# Beam_ADC.net
KiCad netlist of a schematic drawn in Altium Designer
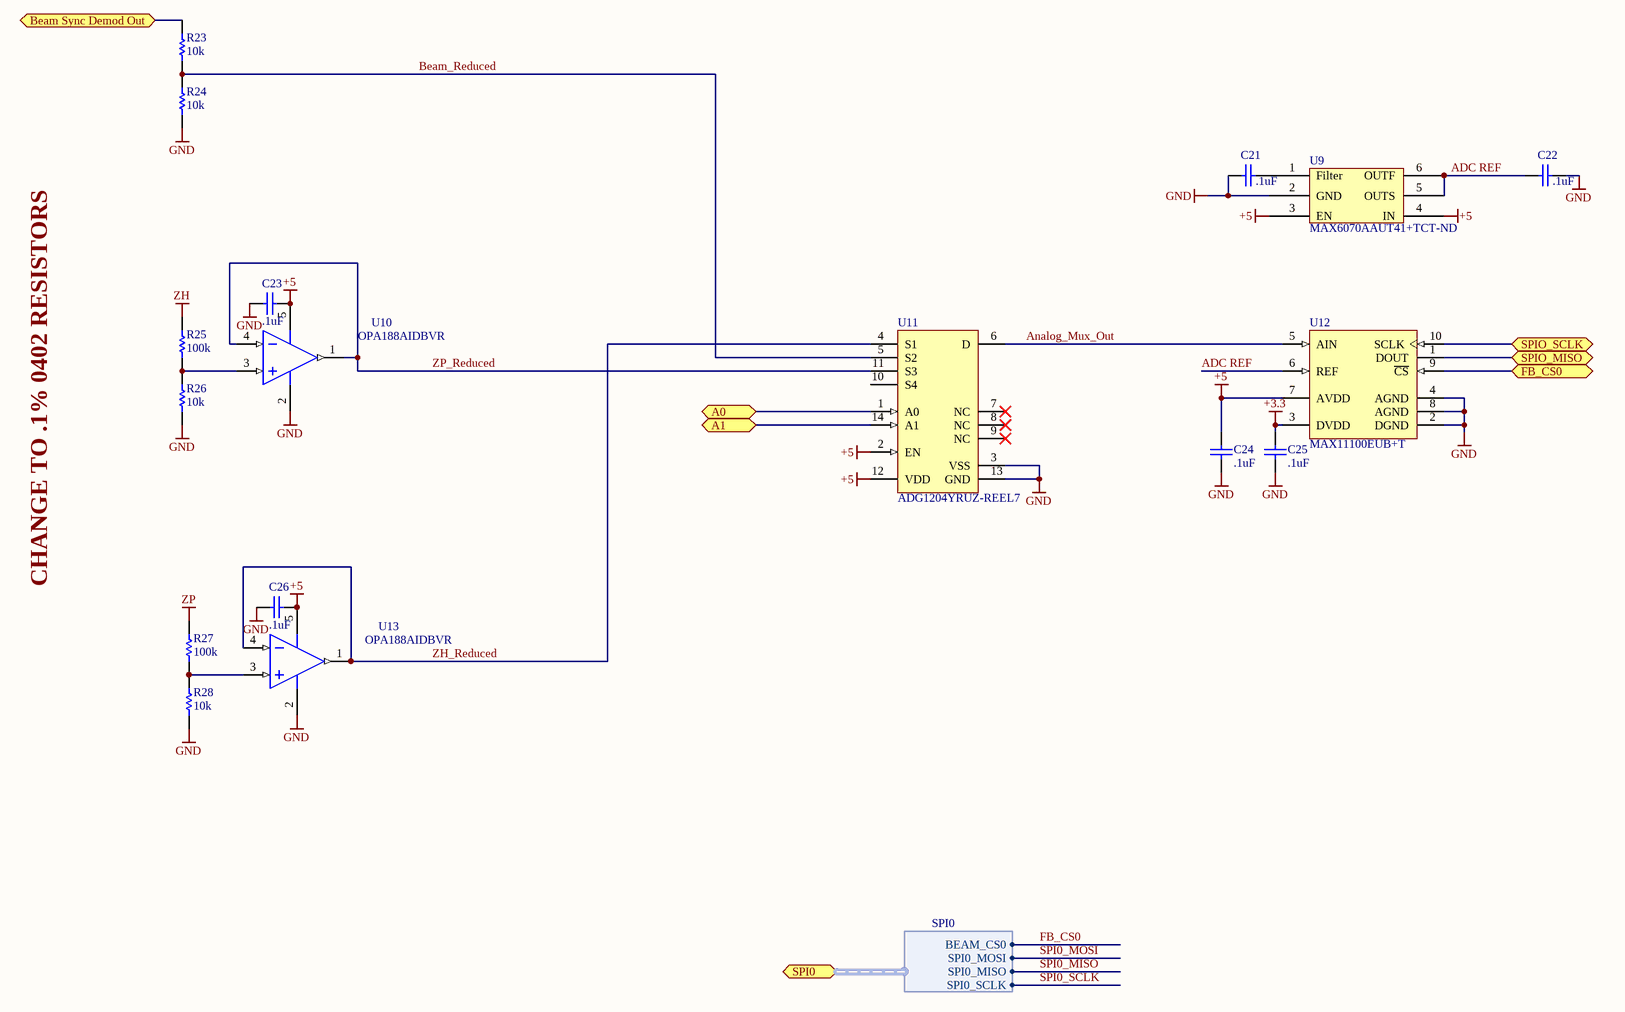
[diagram p0: Beam_ADC.SchDoc]

(export (version "E")
  (design (tool "Eeschema 10.0.6"))
  (components
    (comp (ref "C21")
      (value ".1uF")
      (footprint "CAPC0805(2012)75_N")
      (description "CAP 33pF 25V ±2% 0805 (2012 Metric) Thickness 0.75mm SMD")
      (fields (field (name "TOLERANCE") "Â±2%"))
      (libsource (lib "Altium Content Vault") (part "CMP-1036-01414-1"))
    )
    (comp (ref "C22")
      (value ".1uF")
      (footprint "CAPC0805(2012)75_N")
      (description "CAP 33pF 25V ±2% 0805 (2012 Metric) Thickness 0.75mm SMD")
      (fields (field (name "TOLERANCE") "Â±2%"))
      (libsource (lib "Altium Content Vault") (part "CMP-1036-01414-1"))
    )
    (comp (ref "C23")
      (value ".1uF")
      (footprint "CAPC0805(2012)75_N")
      (description "CAP 33pF 25V ±2% 0805 (2012 Metric) Thickness 0.75mm SMD")
      (fields (field (name "TOLERANCE") "Â±2%"))
      (libsource (lib "Altium Content Vault") (part "CMP-1036-01414-1"))
    )
    (comp (ref "C24")
      (value ".1uF")
      (footprint "CAPC0805(2012)75_N")
      (description "CAP 33pF 25V ±2% 0805 (2012 Metric) Thickness 0.75mm SMD")
      (fields (field (name "TOLERANCE") "Â±2%"))
      (libsource (lib "Altium Content Vault") (part "CMP-1036-01414-1"))
    )
    (comp (ref "C25")
      (value ".1uF")
      (footprint "CAPC0805(2012)75_N")
      (description "CAP 33pF 25V ±2% 0805 (2012 Metric) Thickness 0.75mm SMD")
      (fields (field (name "TOLERANCE") "Â±2%"))
      (libsource (lib "Altium Content Vault") (part "CMP-1036-01414-1"))
    )
    (comp (ref "C26")
      (value ".1uF")
      (footprint "CAPC0805(2012)75_N")
      (description "CAP 33pF 25V ±2% 0805 (2012 Metric) Thickness 0.75mm SMD")
      (fields (field (name "TOLERANCE") "Â±2%"))
      (libsource (lib "Altium Content Vault") (part "CMP-1036-01414-1"))
    )
    (comp (ref "R23")
      (value "10k")
      (footprint "RESC0805(2012)_L")
      (description "2R55 0.125W 1% 0805 (2012 Metric)  SMD")
      (fields (field (name "TOLERANCE") "1 %") (field (name "POWER") "0.125 W"))
      (libsource (lib "Altium Content Vault") (part "CMP-1013-00215-1"))
    )
    (comp (ref "R24")
      (value "10k")
      (footprint "RESC0805(2012)_L")
      (description "2R55 0.125W 1% 0805 (2012 Metric)  SMD")
      (fields (field (name "TOLERANCE") "1 %") (field (name "POWER") "0.125 W"))
      (libsource (lib "Altium Content Vault") (part "CMP-1013-00215-1"))
    )
    (comp (ref "R25")
      (value "100k")
      (footprint "RESC0805(2012)_L")
      (description "2R55 0.125W 1% 0805 (2012 Metric)  SMD")
      (fields (field (name "TOLERANCE") "1 %") (field (name "POWER") "0.125 W"))
      (libsource (lib "Altium Content Vault") (part "CMP-1013-00215-1"))
    )
    (comp (ref "R26")
      (value "10k")
      (footprint "RESC0805(2012)_L")
      (description "2R55 0.125W 1% 0805 (2012 Metric)  SMD")
      (fields (field (name "TOLERANCE") "1 %") (field (name "POWER") "0.125 W"))
      (libsource (lib "Altium Content Vault") (part "CMP-1013-00215-1"))
    )
    (comp (ref "R27")
      (value "100k")
      (footprint "RESC0805(2012)_L")
      (description "2R55 0.125W 1% 0805 (2012 Metric)  SMD")
      (fields (field (name "TOLERANCE") "1 %") (field (name "POWER") "0.125 W"))
      (libsource (lib "Altium Content Vault") (part "CMP-1013-00215-1"))
    )
    (comp (ref "R28")
      (value "10k")
      (footprint "RESC0805(2012)_L")
      (description "2R55 0.125W 1% 0805 (2012 Metric)  SMD")
      (fields (field (name "TOLERANCE") "1 %") (field (name "POWER") "0.125 W"))
      (libsource (lib "Altium Content Vault") (part "CMP-1013-00215-1"))
    )
    (comp (ref "U9")
      (value "MAX6070AAUT41+T")
      (footprint "SOT95P280X445-6N")
      (description "IC VREF SERIES 4.096V SOT23")
      (fields
        (field (name "SUPPLIER PART NUMBER 1") "MAX6070AAUT41+TCT-ND")
        (field (name "MANUFACTURER") "Maxim Integrated")
        (field (name "TOLERANCE") "±0.04%")
      )
      (libsource (lib "ZLS_Schematic_lib") (part "MAX6070AAUT41+T"))
    )
    (comp (ref "U10")
      (value "OPA188AIDBVR")
      (footprint "DBV0005A_M")
      (fields (field (name "MANUFACTURER") "Texas Instruments"))
      (libsource (lib "Altium Content Vault") (part "CMP-0809-00005-2"))
    )
    (comp (ref "U11")
      (value "ADG1204YRUZ-REEL7")
      (footprint "ADI-RU-14_L")
      (fields (field (name "MANUFACTURER") "Analog Devices"))
      (libsource (lib "Altium Content Vault") (part "ADI-ADG1204-RU-14"))
    )
    (comp (ref "U12")
      (value "MAX11100EUB+T")
      (footprint "U10+2_L")
      (description "16-Bit, +5V, 200ksps ADC with 10uA Shutdown, 10-Pin uMAX, -40°C to +85°C, Pb-Free, Tape and Reel")
      (libsource (lib "Altium Content Vault") (part "CON-ADC-MAX11100-IL10"))
    )
    (comp (ref "U13")
      (value "OPA188AIDBVR")
      (footprint "DBV0005A_M")
      (fields (field (name "MANUFACTURER") "Texas Instruments"))
      (libsource (lib "Altium Content Vault") (part "CMP-0809-00005-2"))
    )
  )
  (nets
    (net (code "2") (name "+3.3") (class "Default")
      (node (ref "C25") (pin "2") (pinfunction "2_2") (pintype "passive"))
      (node (ref "U12") (pin "3") (pinfunction "DVDD_3") (pintype "power_in"))
    )
    (net (code "3") (name "+5") (class "Default")
      (node (ref "C23") (pin "2") (pinfunction "2_2") (pintype "passive"))
      (node (ref "C24") (pin "2") (pinfunction "2_2") (pintype "passive"))
      (node (ref "C26") (pin "2") (pinfunction "2_2") (pintype "passive"))
      (node (ref "U10") (pin "5") (pinfunction "V+_5") (pintype "power_in"))
      (node (ref "U11") (pin "12") (pinfunction "VDD_12") (pintype "power_in"))
      (node (ref "U11") (pin "2") (pinfunction "EN_2") (pintype "input"))
      (node (ref "U12") (pin "7") (pinfunction "AVDD_7") (pintype "power_in"))
      (node (ref "U13") (pin "5") (pinfunction "V+_5") (pintype "power_in"))
      (node (ref "U9") (pin "3") (pinfunction "EN_3") (pintype "passive"))
      (node (ref "U9") (pin "4") (pinfunction "IN_4") (pintype "passive"))
    )
    (net (code "4") (name "/A0") (class "Default")
      (node (ref "U11") (pin "1") (pinfunction "A0_1") (pintype "input"))
    )
    (net (code "5") (name "/A1") (class "Default")
      (node (ref "U11") (pin "14") (pinfunction "A1_14") (pintype "input"))
    )
    (net (code "6") (name "/ADC REF") (class "Default")
      (node (ref "C22") (pin "2") (pinfunction "2_2") (pintype "passive"))
      (node (ref "U12") (pin "6") (pinfunction "REF_6") (pintype "input"))
      (node (ref "U9") (pin "5") (pinfunction "OUTS_5") (pintype "passive"))
      (node (ref "U9") (pin "6") (pinfunction "OUTF_6") (pintype "passive"))
    )
    (net (code "7") (name "/Analog_Mux_Out") (class "Default")
      (node (ref "U11") (pin "6") (pinfunction "D_6") (pintype "passive"))
      (node (ref "U12") (pin "5") (pinfunction "AIN_5") (pintype "input"))
    )
    (net (code "8") (name "/Beam Sync Demod Out") (class "Default")
      (node (ref "R23") (pin "2") (pinfunction "2_2") (pintype "passive"))
    )
    (net (code "9") (name "/Beam_Reduced") (class "Default")
      (node (ref "R23") (pin "1") (pinfunction "1_1") (pintype "passive"))
      (node (ref "R24") (pin "2") (pinfunction "2_2") (pintype "passive"))
      (node (ref "U11") (pin "5") (pinfunction "S2_5") (pintype "passive"))
    )
    (net (code "10") (name "/FB_CS0") (class "Default")
      (node (ref "U12") (pin "9") (pinfunction "~{CS}_9") (pintype "input"))
    )
    (net (code "14") (name "/SPIO_MISO") (class "Default")
      (node (ref "U12") (pin "1") (pinfunction "DOUT_1") (pintype "tri_state"))
    )
    (net (code "15") (name "/SPIO_SCLK") (class "Default")
      (node (ref "U12") (pin "10") (pinfunction "SCLK_10") (pintype "input"))
    )
    (net (code "16") (name "/ZH_Reduced") (class "Default")
      (node (ref "U11") (pin "4") (pinfunction "S1_4") (pintype "passive"))
      (node (ref "U13") (pin "1") (pinfunction "OUT_1") (pintype "output"))
      (node (ref "U13") (pin "4") (pinfunction "IN-_4") (pintype "input"))
    )
    (net (code "17") (name "/ZP_Reduced") (class "Default")
      (node (ref "U10") (pin "1") (pinfunction "OUT_1") (pintype "output"))
      (node (ref "U10") (pin "4") (pinfunction "IN-_4") (pintype "input"))
      (node (ref "U11") (pin "11") (pinfunction "S3_11") (pintype "passive"))
    )
    (net (code "19") (name "GND") (class "Default")
      (node (ref "C21") (pin "2") (pinfunction "2_2") (pintype "passive"))
      (node (ref "C22") (pin "1") (pinfunction "1_1") (pintype "passive"))
      (node (ref "C23") (pin "1") (pinfunction "1_1") (pintype "passive"))
      (node (ref "C24") (pin "1") (pinfunction "1_1") (pintype "passive"))
      (node (ref "C25") (pin "1") (pinfunction "1_1") (pintype "passive"))
      (node (ref "C26") (pin "1") (pinfunction "1_1") (pintype "passive"))
      (node (ref "R24") (pin "1") (pinfunction "1_1") (pintype "passive"))
      (node (ref "R26") (pin "1") (pinfunction "1_1") (pintype "passive"))
      (node (ref "R28") (pin "1") (pinfunction "1_1") (pintype "passive"))
      (node (ref "U10") (pin "2") (pinfunction "V-_2") (pintype "power_in"))
      (node (ref "U11") (pin "13") (pinfunction "GND_13") (pintype "power_in"))
      (node (ref "U11") (pin "3") (pinfunction "VSS_3") (pintype "power_in"))
      (node (ref "U12") (pin "2") (pinfunction "DGND_2") (pintype "power_in"))
      (node (ref "U12") (pin "4") (pinfunction "AGND_4") (pintype "power_in"))
      (node (ref "U12") (pin "8") (pinfunction "AGND_8") (pintype "power_in"))
      (node (ref "U13") (pin "2") (pinfunction "V-_2") (pintype "power_in"))
      (node (ref "U9") (pin "2") (pinfunction "GND_2") (pintype "passive"))
    )
    (net (code "20") (name "Net-(U9-Filter)") (class "Default")
      (node (ref "C21") (pin "1") (pinfunction "1_1") (pintype "passive"))
      (node (ref "U9") (pin "1") (pinfunction "Filter_1") (pintype "passive"))
    )
    (net (code "21") (name "Net-(U10-IN+)") (class "Default")
      (node (ref "R25") (pin "1") (pinfunction "1_1") (pintype "passive"))
      (node (ref "R26") (pin "2") (pinfunction "2_2") (pintype "passive"))
      (node (ref "U10") (pin "3") (pinfunction "IN+_3") (pintype "input"))
    )
    (net (code "22") (name "Net-(U13-IN+)") (class "Default")
      (node (ref "R27") (pin "1") (pinfunction "1_1") (pintype "passive"))
      (node (ref "R28") (pin "2") (pinfunction "2_2") (pintype "passive"))
      (node (ref "U13") (pin "3") (pinfunction "IN+_3") (pintype "input"))
    )
    (net (code "23") (name "ZH") (class "Default")
      (node (ref "R25") (pin "2") (pinfunction "2_2") (pintype "passive"))
    )
    (net (code "24") (name "ZP") (class "Default")
      (node (ref "R27") (pin "2") (pinfunction "2_2") (pintype "passive"))
    )
    (net (code "25") (name "unconnected-(U11-NC-Pad7)") (class "Default")
      (node (ref "U11") (pin "7") (pinfunction "NC_7") (pintype "passive+no_connect"))
    )
    (net (code "26") (name "unconnected-(U11-NC-Pad8)") (class "Default")
      (node (ref "U11") (pin "8") (pinfunction "NC_8") (pintype "passive+no_connect"))
    )
    (net (code "27") (name "unconnected-(U11-NC-Pad9)") (class "Default")
      (node (ref "U11") (pin "9") (pinfunction "NC_9") (pintype "passive+no_connect"))
    )
    (net (code "28") (name "unconnected-(U11-S4-Pad10)") (class "Default")
      (node (ref "U11") (pin "10") (pinfunction "S4_10") (pintype "passive"))
    )
  )
)
